# RJ-45_Dash_Daughter_Board.net
KiCad netlist of a schematic drawn in EAGLE
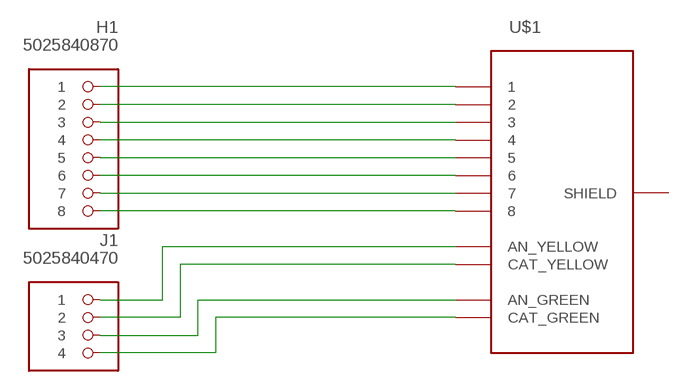
[diagram p0: schematic, sheet 1]

(export (version "E")
  (design (tool "Eeschema 10.0.6"))
  (components
    (comp (ref "H1")
      (value "5025840870")
      (footprint "eagle-import:MOLEX-CLIKMATE-8-VERTICAL-HEADER")
      (libsource (lib "eagle-import") (part "MOLEX_CLICKMATE-8-VERTICAL"))
    )
    (comp (ref "J1")
      (value "5025840470")
      (footprint "eagle-import:MOLEX-CLIKMATE-4-VERTICAL-HEADER")
      (libsource (lib "eagle-import") (part "MOLEX_CLICKMATE-4-VERTICAL"))
    )
    (comp (ref "U$1")
      (value "RJ-45_12-PIN")
      (footprint "eagle-import:RJ-45")
      (libsource (lib "eagle-import") (part "RJ-45_12-PIN"))
    )
  )
  (nets
    (net (code "1") (name "Net-(U$1-1)") (class "Default")
      (node (ref "H1") (pin "1") (pinfunction "1_1") (pintype "bidirectional"))
      (node (ref "U$1") (pin "P$1") (pinfunction "1_P$1") (pintype "bidirectional"))
    )
    (net (code "2") (name "Net-(U$1-2)") (class "Default")
      (node (ref "H1") (pin "2") (pinfunction "2_2") (pintype "bidirectional"))
      (node (ref "U$1") (pin "P$2") (pinfunction "2_P$2") (pintype "bidirectional"))
    )
    (net (code "3") (name "Net-(U$1-3)") (class "Default")
      (node (ref "H1") (pin "3") (pinfunction "3_3") (pintype "bidirectional"))
      (node (ref "U$1") (pin "P$3") (pinfunction "3_P$3") (pintype "bidirectional"))
    )
    (net (code "4") (name "Net-(U$1-4)") (class "Default")
      (node (ref "H1") (pin "4") (pinfunction "4_4") (pintype "bidirectional"))
      (node (ref "U$1") (pin "P$4") (pinfunction "4_P$4") (pintype "bidirectional"))
    )
    (net (code "5") (name "Net-(U$1-5)") (class "Default")
      (node (ref "H1") (pin "5") (pinfunction "5_5") (pintype "bidirectional"))
      (node (ref "U$1") (pin "P$5") (pinfunction "5_P$5") (pintype "bidirectional"))
    )
    (net (code "6") (name "Net-(U$1-6)") (class "Default")
      (node (ref "H1") (pin "6") (pinfunction "6_6") (pintype "bidirectional"))
      (node (ref "U$1") (pin "P$6") (pinfunction "6_P$6") (pintype "bidirectional"))
    )
    (net (code "7") (name "Net-(U$1-7)") (class "Default")
      (node (ref "H1") (pin "7") (pinfunction "7_7") (pintype "bidirectional"))
      (node (ref "U$1") (pin "P$7") (pinfunction "7_P$7") (pintype "bidirectional"))
    )
    (net (code "8") (name "Net-(U$1-8)") (class "Default")
      (node (ref "H1") (pin "8") (pinfunction "8_8") (pintype "bidirectional"))
      (node (ref "U$1") (pin "P$8") (pinfunction "8_P$8") (pintype "bidirectional"))
    )
    (net (code "9") (name "Net-(U$1-AN_GREEN)") (class "Default")
      (node (ref "J1") (pin "3") (pinfunction "3_3") (pintype "bidirectional"))
      (node (ref "U$1") (pin "P$11") (pinfunction "AN_GREEN_P$11") (pintype "bidirectional"))
    )
    (net (code "10") (name "Net-(U$1-AN_YELLOW)") (class "Default")
      (node (ref "J1") (pin "1") (pinfunction "1_1") (pintype "bidirectional"))
      (node (ref "U$1") (pin "P$9") (pinfunction "AN_YELLOW_P$9") (pintype "bidirectional"))
    )
    (net (code "11") (name "Net-(U$1-CAT_GREEN)") (class "Default")
      (node (ref "J1") (pin "4") (pinfunction "4_4") (pintype "bidirectional"))
      (node (ref "U$1") (pin "P$12") (pinfunction "CAT_GREEN_P$12") (pintype "bidirectional"))
    )
    (net (code "12") (name "Net-(U$1-CAT_YELLOW)") (class "Default")
      (node (ref "J1") (pin "2") (pinfunction "2_2") (pintype "bidirectional"))
      (node (ref "U$1") (pin "P$10") (pinfunction "CAT_YELLOW_P$10") (pintype "bidirectional"))
    )
    (net (code "13") (name "unconnected-(U$1-SHIELD-PadP$13)") (class "Default")
      (node (ref "U$1") (pin "P$13") (pinfunction "SHIELD_P$13") (pintype "bidirectional"))
    )
  )
)
